# Transistor.net
KiCad netlist of a schematic drawn in Altium Designer
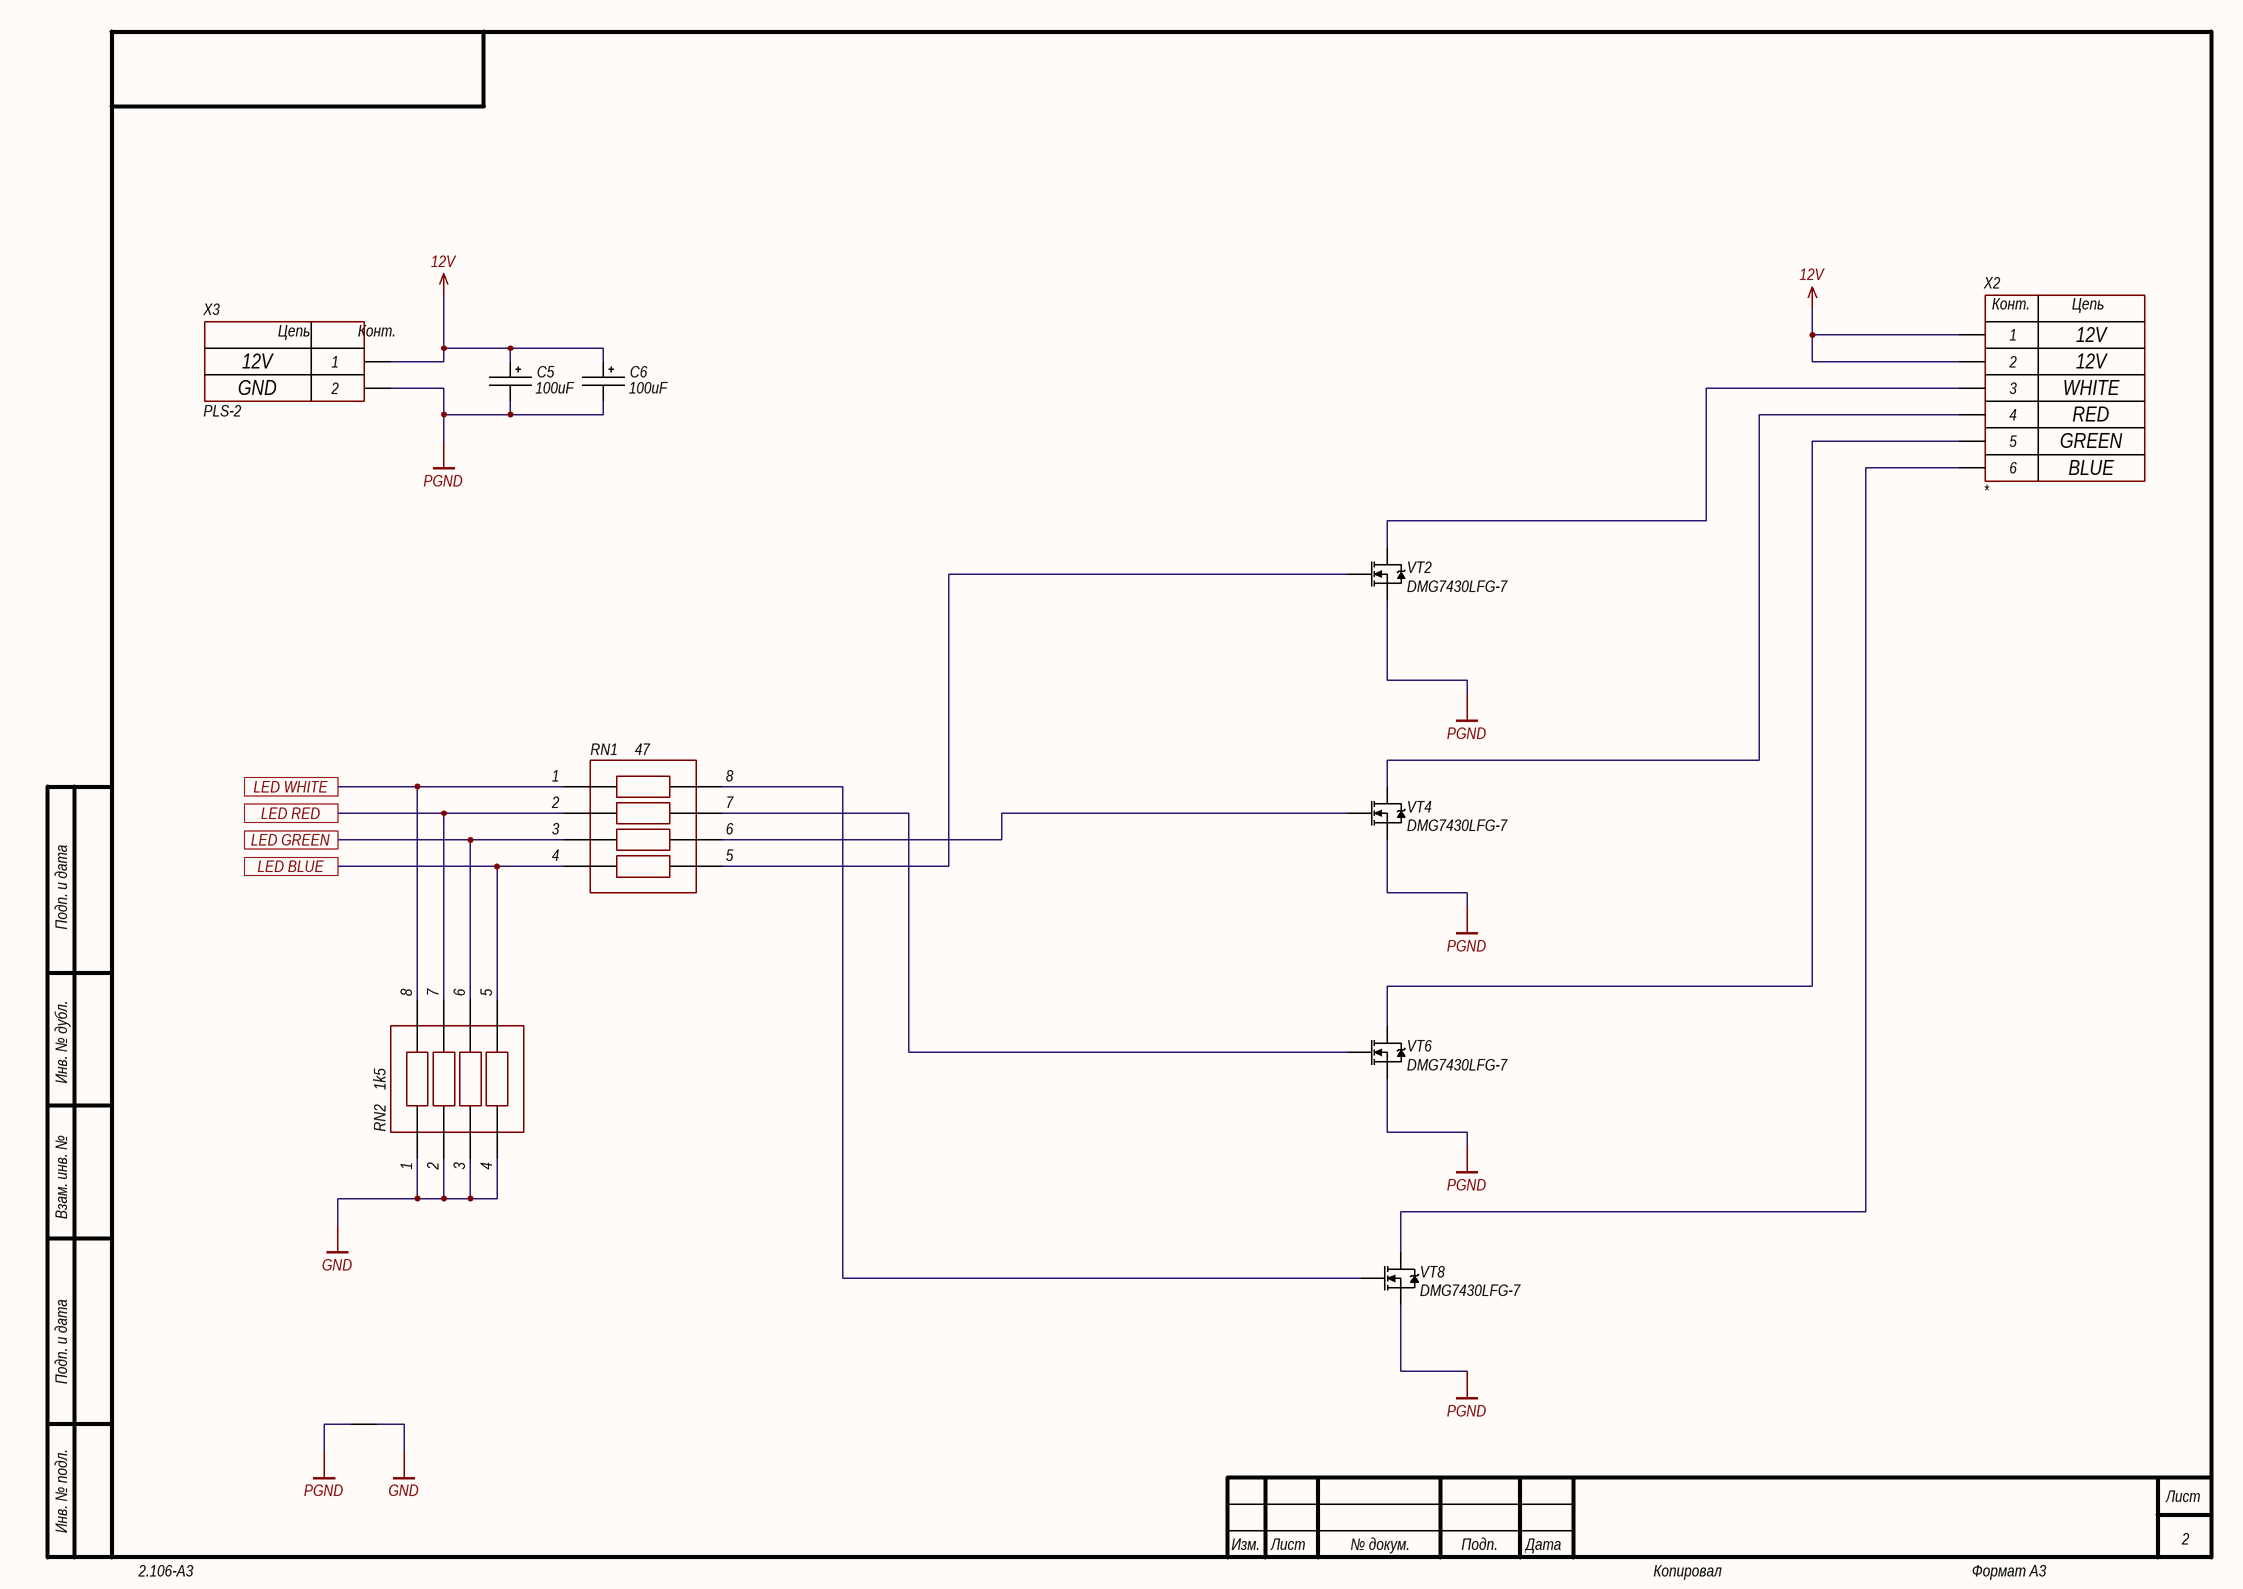
[diagram p0: Transistor.SchDoc]

(export (version "E")
  (design (tool "Eeschema 10.0.6"))
  (components
    (comp (ref "C5") (value "100uF") (footprint "D5C2H11") (libsource (lib "Discrete") (part "AlumCap")))
    (comp (ref "C6") (value "100uF") (footprint "D5C2H11") (libsource (lib "Discrete") (part "AlumCap")))
    (comp (ref "RN1")
      (value "47")
      (footprint "CH0603Rx4 (1206)")
      (fields (field (name "MANUFACTURER") "Bourns GmbH."))
      (libsource (lib "Discrete") (part "Resistor assembly"))
    )
    (comp (ref "RN2")
      (value "1k5")
      (footprint "CH0603Rx4 (1206)")
      (fields (field (name "MANUFACTURER") "Bourns GmbH."))
      (libsource (lib "") (part "Resistor assembly_1"))
    )
    (comp (ref "VT2")
      (value "DMG7430LFG-7")
      (footprint "TRANS: PowerDI®3333-8")
      (description "Mosfet")
      (fields (field (name "MANUFACTURER") "Diodes Incorporated"))
      (libsource (lib "Transistor") (part "N-chanel"))
    )
    (comp (ref "VT4")
      (value "DMG7430LFG-7")
      (footprint "TRANS: PowerDI®3333-8")
      (description "Mosfet")
      (fields (field (name "MANUFACTURER") "Diodes Incorporated"))
      (libsource (lib "Transistor") (part "N-chanel"))
    )
    (comp (ref "VT6")
      (value "DMG7430LFG-7")
      (footprint "TRANS: PowerDI®3333-8")
      (description "Mosfet")
      (fields (field (name "MANUFACTURER") "Diodes Incorporated"))
      (libsource (lib "Transistor") (part "N-chanel"))
    )
    (comp (ref "VT8")
      (value "DMG7430LFG-7")
      (footprint "TRANS: PowerDI®3333-8")
      (description "Mosfet")
      (fields (field (name "MANUFACTURER") "Diodes Incorporated"))
      (libsource (lib "Transistor") (part "N-chanel"))
    )
    (comp (ref "W1")
      (value "Net Tie")
      (footprint "CON: Net Tie")
      (libsource (lib "Connectors") (part "Net Tie"))
    )
    (comp (ref "X2") (value "*") (footprint "CON: PLS-6") (libsource (lib "Connectors") (part "6-Connector")))
    (comp (ref "X3")
      (value "PLS-2")
      (footprint "CON: PLS-2")
      (libsource (lib "Connectors") (part "2-Connector"))
    )
  )
  (nets
    (net (code "1") (name "/LED BLUE") (class "Default")
      (node (ref "RN1") (pin "4") (pinfunction "4_4") (pintype "passive"))
      (node (ref "RN2") (pin "5") (pinfunction "5_5") (pintype "passive"))
    )
    (net (code "2") (name "/LED GREEN") (class "Default")
      (node (ref "RN1") (pin "3") (pinfunction "3_3") (pintype "passive"))
      (node (ref "RN2") (pin "6") (pinfunction "6_6") (pintype "passive"))
    )
    (net (code "3") (name "/LED RED") (class "Default")
      (node (ref "RN1") (pin "2") (pinfunction "2_2") (pintype "passive"))
      (node (ref "RN2") (pin "7") (pinfunction "7_7") (pintype "passive"))
    )
    (net (code "4") (name "/LED WHITE") (class "Default")
      (node (ref "RN1") (pin "1") (pinfunction "1_1") (pintype "passive"))
      (node (ref "RN2") (pin "8") (pinfunction "8_8") (pintype "passive"))
    )
    (net (code "5") (name "12V") (class "Default")
      (node (ref "C5") (pin "1") (pinfunction "1_1") (pintype "power_in"))
      (node (ref "C6") (pin "1") (pinfunction "1_1") (pintype "power_in"))
      (node (ref "X2") (pin "1") (pinfunction "1_1") (pintype "passive"))
      (node (ref "X2") (pin "2") (pinfunction "2_2") (pintype "passive"))
      (node (ref "X3") (pin "1") (pinfunction "1_1") (pintype "passive"))
    )
    (net (code "6") (name "GND") (class "Default")
      (node (ref "RN2") (pin "1") (pinfunction "1_1") (pintype "passive"))
      (node (ref "RN2") (pin "2") (pinfunction "2_2") (pintype "passive"))
      (node (ref "RN2") (pin "3") (pinfunction "3_3") (pintype "passive"))
      (node (ref "RN2") (pin "4") (pinfunction "4_4") (pintype "passive"))
      (node (ref "W1") (pin "2") (pinfunction "2_2") (pintype "power_in"))
    )
    (net (code "7") (name "Net-(VT2-D)") (class "Default")
      (node (ref "VT2") (pin "2") (pinfunction "D_2") (pintype "passive"))
      (node (ref "X2") (pin "3") (pinfunction "3_3") (pintype "power_in"))
    )
    (net (code "8") (name "Net-(VT2-G)") (class "Default")
      (node (ref "RN1") (pin "5") (pinfunction "5_5") (pintype "passive"))
      (node (ref "VT2") (pin "1") (pinfunction "G_1") (pintype "passive"))
    )
    (net (code "9") (name "Net-(VT4-D)") (class "Default")
      (node (ref "VT4") (pin "2") (pinfunction "D_2") (pintype "passive"))
      (node (ref "X2") (pin "4") (pinfunction "4_4") (pintype "power_in"))
    )
    (net (code "10") (name "Net-(VT4-G)") (class "Default")
      (node (ref "RN1") (pin "6") (pinfunction "6_6") (pintype "passive"))
      (node (ref "VT4") (pin "1") (pinfunction "G_1") (pintype "passive"))
    )
    (net (code "11") (name "Net-(VT6-D)") (class "Default")
      (node (ref "VT6") (pin "2") (pinfunction "D_2") (pintype "passive"))
      (node (ref "X2") (pin "5") (pinfunction "5_5") (pintype "power_in"))
    )
    (net (code "12") (name "Net-(VT6-G)") (class "Default")
      (node (ref "RN1") (pin "7") (pinfunction "7_7") (pintype "passive"))
      (node (ref "VT6") (pin "1") (pinfunction "G_1") (pintype "passive"))
    )
    (net (code "13") (name "Net-(VT8-D)") (class "Default")
      (node (ref "VT8") (pin "2") (pinfunction "D_2") (pintype "passive"))
      (node (ref "X2") (pin "6") (pinfunction "6_6") (pintype "power_in"))
    )
    (net (code "14") (name "Net-(VT8-G)") (class "Default")
      (node (ref "RN1") (pin "8") (pinfunction "8_8") (pintype "passive"))
      (node (ref "VT8") (pin "1") (pinfunction "G_1") (pintype "passive"))
    )
    (net (code "15") (name "PGND") (class "Default")
      (node (ref "C5") (pin "2") (pinfunction "2_2") (pintype "power_in"))
      (node (ref "C6") (pin "2") (pinfunction "2_2") (pintype "power_in"))
      (node (ref "VT2") (pin "3") (pinfunction "S_3") (pintype "passive"))
      (node (ref "VT4") (pin "3") (pinfunction "S_3") (pintype "passive"))
      (node (ref "VT6") (pin "3") (pinfunction "S_3") (pintype "passive"))
      (node (ref "VT8") (pin "3") (pinfunction "S_3") (pintype "passive"))
      (node (ref "W1") (pin "1") (pinfunction "1_1") (pintype "power_in"))
      (node (ref "X3") (pin "2") (pinfunction "2_2") (pintype "passive"))
    )
  )
)
